# TsinghuaDoor_bottom.net
KiCad netlist of a schematic drawn in Altium Designer
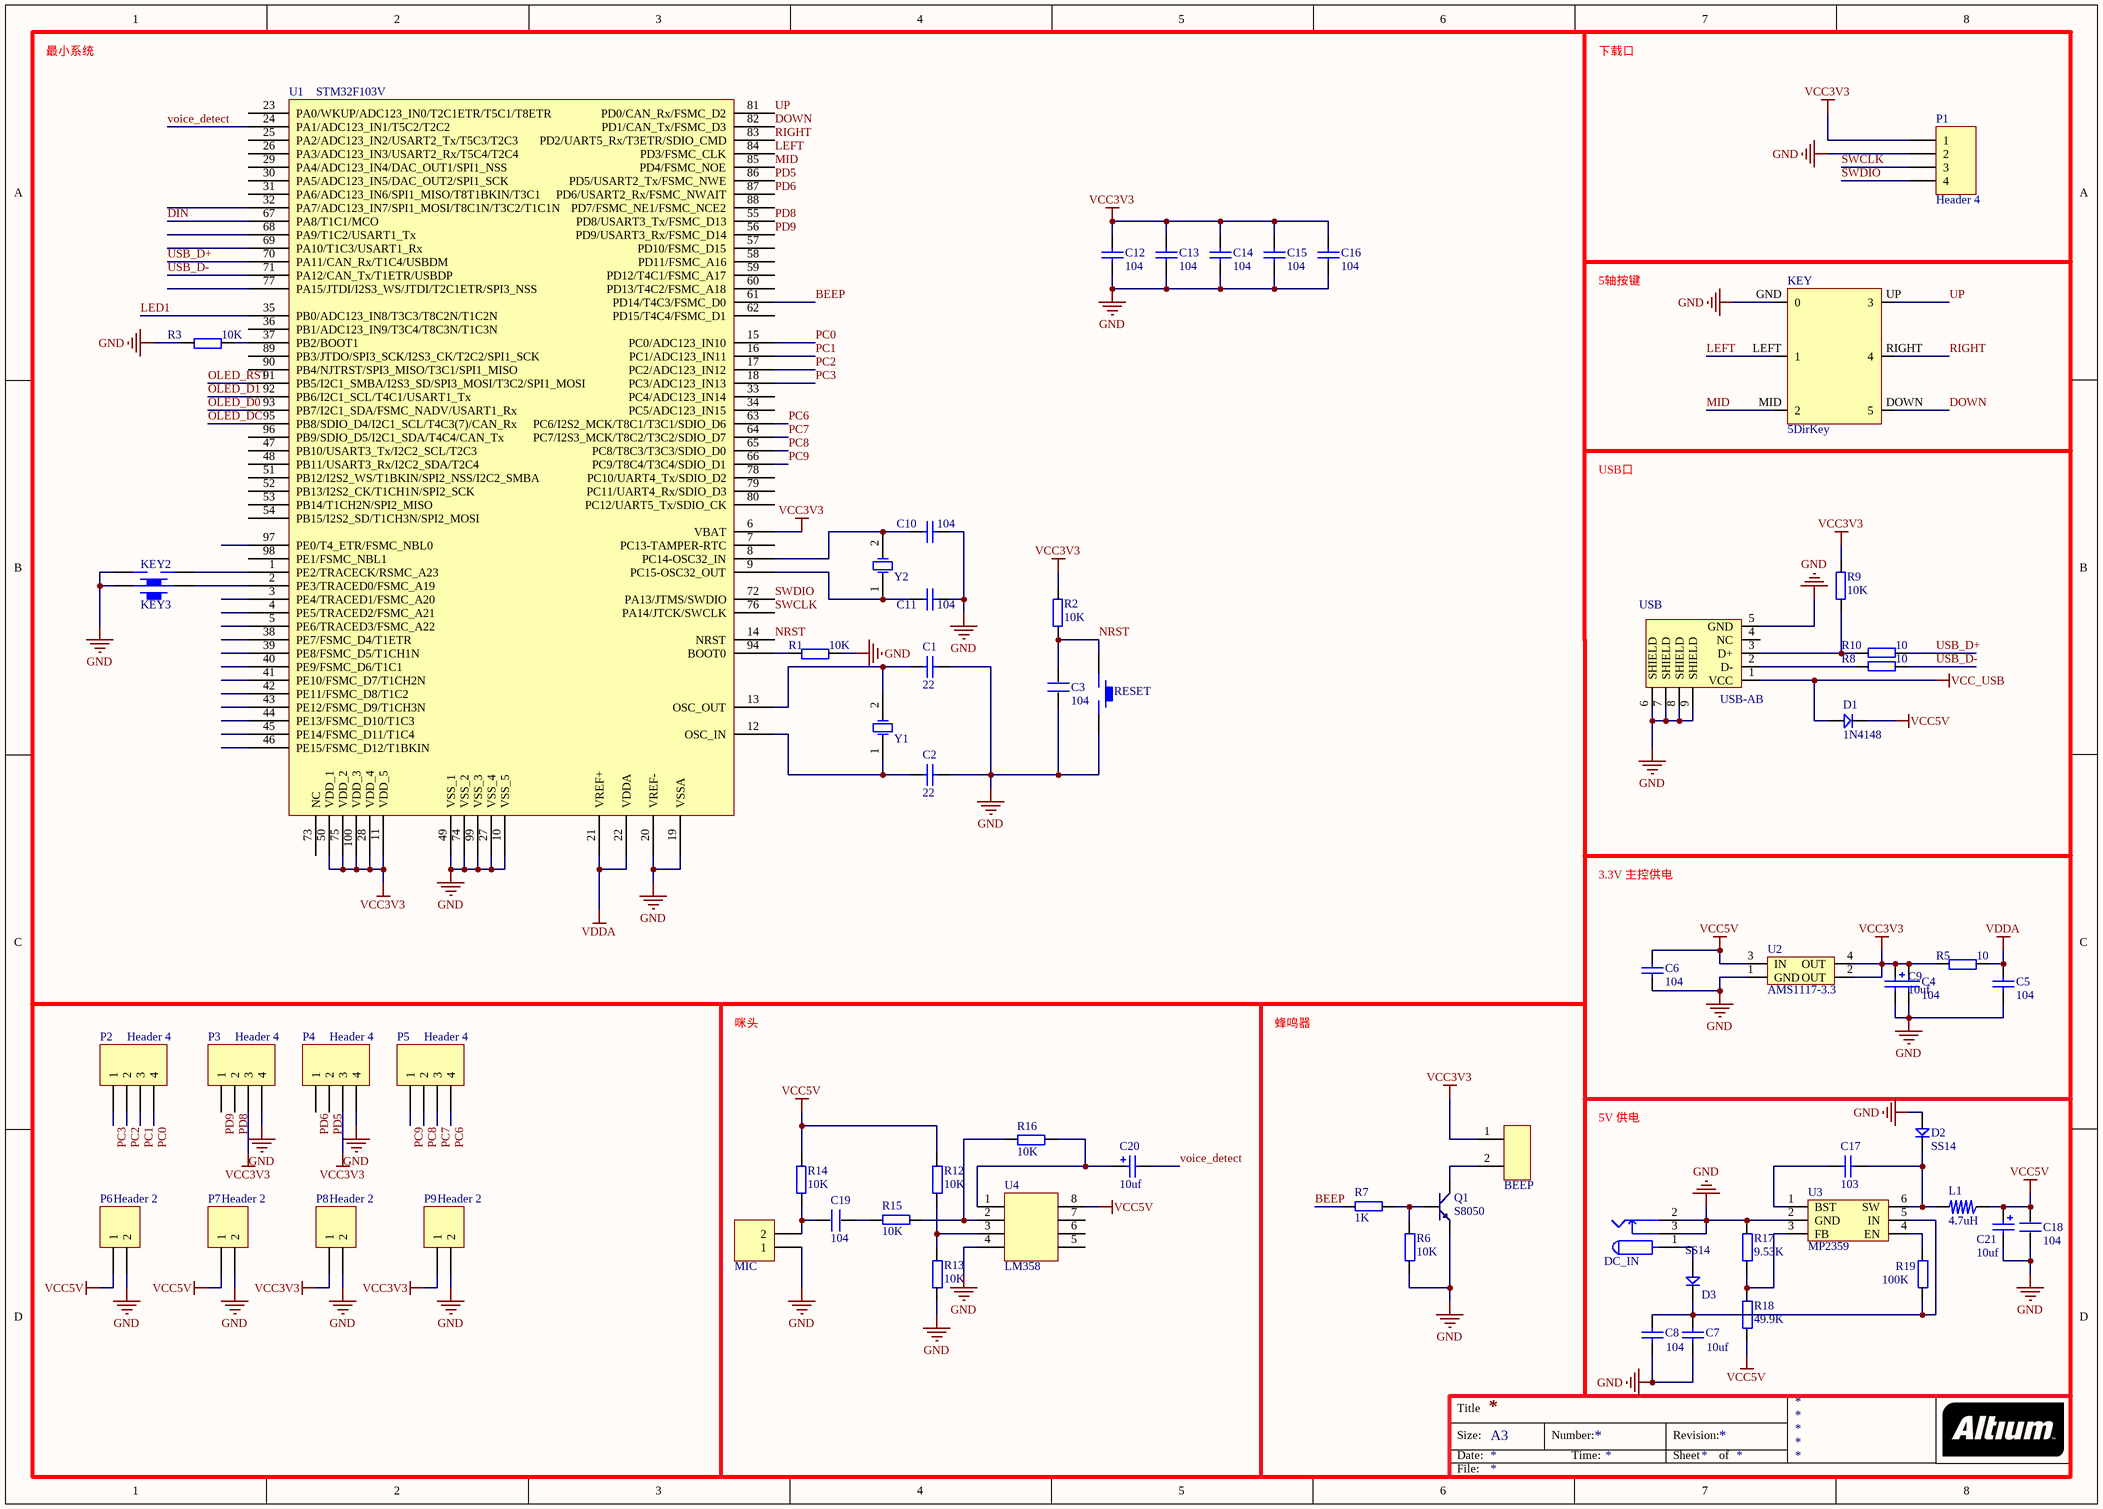
[diagram p0: TsinghuaDoor_bottom.SchDoc]

(export (version "E")
  (design (tool "Eeschema 10.0.6"))
  (components
    (comp (ref "BEEP") (value "蜂鸣器") (footprint "蜂鸣器-7.6mm") (libsource (lib "常用元件集成库") (part "蜂鸣器")))
    (comp (ref "C1")
      (value "22")
      (footprint "cap_0603 - duplicate")
      (description "Capacitor")
      (fields (field (name "Comment") "Cap") (field (name "PUBLISHER") "Altium Limited"))
      (libsource (lib "常用元件集成库") (part "Cap"))
    )
    (comp (ref "C2")
      (value "22")
      (footprint "cap_0603 - duplicate")
      (description "Capacitor")
      (fields (field (name "Comment") "Cap") (field (name "PUBLISHER") "Altium Limited"))
      (libsource (lib "常用元件集成库") (part "Cap"))
    )
    (comp (ref "C3") (value "104") (footprint "0603P") (libsource (lib "阿波罗STM32F4&F7底板封装库") (part "C")))
    (comp (ref "C4")
      (value "104")
      (footprint "cap_0603 - duplicate")
      (description "Capacitor")
      (fields (field (name "Comment") "Cap") (field (name "PUBLISHER") "Altium Limited"))
      (libsource (lib "常用元件集成库") (part "Cap"))
    )
    (comp (ref "C5")
      (value "104")
      (footprint "cap_0603 - duplicate")
      (description "Capacitor")
      (fields (field (name "Comment") "Cap") (field (name "PUBLISHER") "Altium Limited"))
      (libsource (lib "常用元件集成库") (part "Cap"))
    )
    (comp (ref "C6")
      (value "104")
      (footprint "cap_0603 - duplicate")
      (description "Capacitor")
      (fields (field (name "Comment") "Cap") (field (name "PUBLISHER") "Altium Limited"))
      (libsource (lib "常用元件集成库") (part "Cap"))
    )
    (comp (ref "C7")
      (value "10uf")
      (footprint "电容-0805")
      (description "Capacitor")
      (fields (field (name "Comment") "Cap") (field (name "PUBLISHER") "Altium Limited"))
      (libsource (lib "常用元件集成库") (part "Cap"))
    )
    (comp (ref "C8")
      (value "104")
      (footprint "电容-0805")
      (description "Capacitor")
      (fields (field (name "Comment") "Cap") (field (name "PUBLISHER") "Altium Limited"))
      (libsource (lib "常用元件集成库") (part "Cap"))
    )
    (comp (ref "C9")
      (value "10uf")
      (footprint "电容-6032")
      (description "Polarized Capacitor (Radial)")
      (fields (field (name "Comment") "Cap Pol") (field (name "PUBLISHER") "Altium Limited"))
      (libsource (lib "常用元件集成库") (part "Cap Pol"))
    )
    (comp (ref "C10")
      (value "104")
      (footprint "cap_0603 - duplicate")
      (description "Capacitor")
      (fields (field (name "Comment") "Cap") (field (name "PUBLISHER") "Altium Limited"))
      (libsource (lib "常用元件集成库") (part "Cap"))
    )
    (comp (ref "C11")
      (value "104")
      (footprint "cap_0603 - duplicate")
      (description "Capacitor")
      (fields (field (name "Comment") "Cap") (field (name "PUBLISHER") "Altium Limited"))
      (libsource (lib "常用元件集成库") (part "Cap"))
    )
    (comp (ref "C12")
      (value "104")
      (footprint "cap_0603 - duplicate")
      (description "Capacitor")
      (fields (field (name "Comment") "Cap") (field (name "PUBLISHER") "Altium Limited"))
      (libsource (lib "常用元件集成库") (part "Cap"))
    )
    (comp (ref "C13")
      (value "104")
      (footprint "cap_0603 - duplicate")
      (description "Capacitor")
      (fields (field (name "Comment") "Cap") (field (name "PUBLISHER") "Altium Limited"))
      (libsource (lib "常用元件集成库") (part "Cap"))
    )
    (comp (ref "C14")
      (value "104")
      (footprint "cap_0603 - duplicate")
      (description "Capacitor")
      (fields (field (name "Comment") "Cap") (field (name "PUBLISHER") "Altium Limited"))
      (libsource (lib "常用元件集成库") (part "Cap"))
    )
    (comp (ref "C15")
      (value "104")
      (footprint "cap_0603 - duplicate")
      (description "Capacitor")
      (fields (field (name "Comment") "Cap") (field (name "PUBLISHER") "Altium Limited"))
      (libsource (lib "常用元件集成库") (part "Cap"))
    )
    (comp (ref "C16")
      (value "104")
      (footprint "cap_0603 - duplicate")
      (description "Capacitor")
      (fields (field (name "Comment") "Cap") (field (name "PUBLISHER") "Altium Limited"))
      (libsource (lib "常用元件集成库") (part "Cap"))
    )
    (comp (ref "C17")
      (value "103")
      (footprint "电容-0805")
      (description "Capacitor")
      (fields (field (name "Comment") "Cap") (field (name "PUBLISHER") "Altium Limited"))
      (libsource (lib "常用元件集成库") (part "Cap"))
    )
    (comp (ref "C18") (value "104") (footprint "0603P") (libsource (lib "阿波罗STM32F4&F7底板封装库") (part "C")))
    (comp (ref "C19") (value "104") (footprint "1206") (libsource (lib "阿波罗STM32F4&F7底板封装库") (part "C")))
    (comp (ref "C20")
      (value "10uf")
      (footprint "电容-3528")
      (description "Polarized Capacitor (Radial)")
      (fields (field (name "Comment") "Cap Pol") (field (name "PUBLISHER") "Altium Limited"))
      (libsource (lib "常用元件集成库") (part "Cap Pol"))
    )
    (comp (ref "C21")
      (value "10uf")
      (footprint "电容-6032")
      (description "Polarized Capacitor (Radial)")
      (fields (field (name "Comment") "Cap Pol") (field (name "PUBLISHER") "Altium Limited"))
      (libsource (lib "常用元件集成库") (part "Cap Pol"))
    )
    (comp (ref "D1")
      (value "1N4148")
      (footprint "DIODE_3*5.3")
      (libsource (lib "阿波罗STM32F4&F7底板封装库") (part "D"))
    )
    (comp (ref "D2")
      (value "SS14")
      (footprint "DIODE_3*5.3")
      (libsource (lib "阿波罗STM32F4&F7底板封装库") (part "D"))
    )
    (comp (ref "D3")
      (value "SS14")
      (footprint "DIODE_3*5.3")
      (libsource (lib "阿波罗STM32F4&F7底板封装库") (part "D"))
    )
    (comp (ref "DC_IN")
      (value "POWER")
      (footprint "DC10B")
      (libsource (lib "阿波罗STM32F4&F7底板封装库") (part "POW"))
    )
    (comp (ref "KEY") (value "5DirKey") (footprint "5DirKey") (libsource (lib "常用元件集成库") (part "5DirKey")))
    (comp (ref "KEY2")
      (value "KEY_M")
      (footprint "KEY_M")
      (libsource (lib "阿波罗STM32F4&F7底板封装库") (part "KEY_M"))
    )
    (comp (ref "KEY3")
      (value "KEY_M")
      (footprint "KEY_M")
      (libsource (lib "阿波罗STM32F4&F7底板封装库") (part "KEY_M"))
    )
    (comp (ref "L1")
      (value "4.7uH")
      (footprint "L_SOP74")
      (libsource (lib "阿波罗STM32F4&F7底板封装库") (part "L_SOP"))
    )
    (comp (ref "MIC")
      (value "VREF_SEL")
      (footprint "HDR1X2")
      (description "Header, 2-Pin")
      (fields (field (name "PUBLISHER") "Altium Limited"))
      (libsource (lib "阿波罗STM32F4&F7底板封装库") (part "Header 2"))
    )
    (comp (ref "P1")
      (value "Header 4")
      (footprint "HDR1X4")
      (description "Header, 4-Pin")
      (fields (field (name "PUBLISHER") "Altium Limited"))
      (libsource (lib "阿波罗STM32F4&F7底板封装库") (part "Header 4"))
    )
    (comp (ref "P2")
      (value "Header 4")
      (footprint "Header-1*4-2.54mm")
      (description "Header, 4-Pin")
      (fields (field (name "PUBLISHER") "Altium Limited"))
      (libsource (lib "接插件集成库") (part "Header 4"))
    )
    (comp (ref "P3")
      (value "Header 4")
      (footprint "Header-1*4-2.54mm")
      (description "Header, 4-Pin")
      (fields (field (name "PUBLISHER") "Altium Limited"))
      (libsource (lib "接插件集成库") (part "Header 4"))
    )
    (comp (ref "P4")
      (value "Header 4")
      (footprint "Header-1*4-2.54mm")
      (description "Header, 4-Pin")
      (fields (field (name "PUBLISHER") "Altium Limited"))
      (libsource (lib "接插件集成库") (part "Header 4"))
    )
    (comp (ref "P5")
      (value "Header 4")
      (footprint "Header-1*4-2.54mm")
      (description "Header, 4-Pin")
      (fields (field (name "PUBLISHER") "Altium Limited"))
      (libsource (lib "接插件集成库") (part "Header 4"))
    )
    (comp (ref "P6")
      (value "Header 2")
      (footprint "Header-1*2-2.54mm")
      (description "Header, 2-Pin")
      (fields (field (name "PUBLISHER") "Altium Limited"))
      (libsource (lib "接插件集成库") (part "Header 2"))
    )
    (comp (ref "P7")
      (value "Header 2")
      (footprint "Header-1*2-2.54mm")
      (description "Header, 2-Pin")
      (fields (field (name "PUBLISHER") "Altium Limited"))
      (libsource (lib "接插件集成库") (part "Header 2"))
    )
    (comp (ref "P8")
      (value "Header 2")
      (footprint "Header-1*2-2.54mm")
      (description "Header, 2-Pin")
      (fields (field (name "PUBLISHER") "Altium Limited"))
      (libsource (lib "接插件集成库") (part "Header 2"))
    )
    (comp (ref "P9")
      (value "Header 2")
      (footprint "Header-1*2-2.54mm")
      (description "Header, 2-Pin")
      (fields (field (name "PUBLISHER") "Altium Limited"))
      (libsource (lib "接插件集成库") (part "Header 2"))
    )
    (comp (ref "Q1")
      (value "S8050")
      (footprint "SOT-23R")
      (description "8050/BCW846/BCW847")
      (libsource (lib "阿波罗STM32F4&F7底板封装库") (part "NPN"))
    )
    (comp (ref "R1") (value "10K") (footprint "0603P") (libsource (lib "阿波罗STM32F4&F7底板封装库") (part "R")))
    (comp (ref "R2") (value "10K") (footprint "0603P") (libsource (lib "阿波罗STM32F4&F7底板封装库") (part "R")))
    (comp (ref "R3") (value "10K") (footprint "0603P") (libsource (lib "阿波罗STM32F4&F7底板封装库") (part "R")))
    (comp (ref "R5") (value "10") (footprint "0603P") (libsource (lib "阿波罗STM32F4&F7底板封装库") (part "R")))
    (comp (ref "R6") (value "10K") (footprint "0603P") (libsource (lib "阿波罗STM32F4&F7底板封装库") (part "R")))
    (comp (ref "R7") (value "1K") (footprint "0603P") (libsource (lib "阿波罗STM32F4&F7底板封装库") (part "R")))
    (comp (ref "R8") (value "10") (footprint "0603P") (libsource (lib "阿波罗STM32F4&F7底板封装库") (part "R")))
    (comp (ref "R9") (value "10K") (footprint "0603P") (libsource (lib "阿波罗STM32F4&F7底板封装库") (part "R")))
    (comp (ref "R10") (value "10") (footprint "0603P") (libsource (lib "阿波罗STM32F4&F7底板封装库") (part "R")))
    (comp (ref "R12") (value "10K") (footprint "0603P") (libsource (lib "阿波罗STM32F4&F7底板封装库") (part "R")))
    (comp (ref "R13") (value "10K") (footprint "0603P") (libsource (lib "阿波罗STM32F4&F7底板封装库") (part "R")))
    (comp (ref "R14") (value "10K") (footprint "0603P") (libsource (lib "阿波罗STM32F4&F7底板封装库") (part "R")))
    (comp (ref "R15") (value "10K") (footprint "0603P") (libsource (lib "阿波罗STM32F4&F7底板封装库") (part "R")))
    (comp (ref "R16") (value "10K") (footprint "0603P") (libsource (lib "阿波罗STM32F4&F7底板封装库") (part "R")))
    (comp (ref "R17") (value "9.53K") (footprint "0603P") (libsource (lib "阿波罗STM32F4&F7底板封装库") (part "R")))
    (comp (ref "R18") (value "49.9K") (footprint "0603P") (libsource (lib "阿波罗STM32F4&F7底板封装库") (part "R")))
    (comp (ref "R19") (value "100K") (footprint "0603P") (libsource (lib "阿波罗STM32F4&F7底板封装库") (part "R")))
    (comp (ref "RESET") (value "KEY_M") (footprint "KEY_M") (libsource (lib "") (part "KEY_M_1")))
    (comp (ref "U1")
      (value "STM32F103V")
      (footprint "LQFP-100_M")
      (description "STM32单片机100引脚")
      (libsource (lib "主控芯片集成库") (part "STM32F103V"))
    )
    (comp (ref "U2")
      (value "AMS1117-3.3")
      (footprint "AMS1117")
      (libsource (lib "阿波罗STM32F4&F7底板封装库") (part "AMS1117"))
    )
    (comp (ref "U3")
      (value "MP2359")
      (footprint "SOT-23-6")
      (description "DC DC Step Down IC")
      (libsource (lib "阿波罗STM32F4&F7底板封装库") (part "MP2359"))
    )
    (comp (ref "U4") (value "LM358") (footprint "SOP-8-4mm") (libsource (lib "IC集成库") (part "IC-8")))
    (comp (ref "USB")
      (value "USB-AB")
      (footprint "USB_AB - 5S - B")
      (description "MicroUSB")
      (libsource (lib "UWB") (part "USB-AB"))
    )
    (comp (ref "Y1")
      (value "晶振")
      (footprint "晶振-DIP2-5.08")
      (description "Crystal Oscillator")
      (fields (field (name "PUBLISHER") "Altium Limited"))
      (libsource (lib "常用元件集成库") (part "晶振"))
    )
    (comp (ref "Y2")
      (value "晶振")
      (footprint "圆柱晶振")
      (description "Crystal Oscillator")
      (fields (field (name "PUBLISHER") "Altium Limited"))
      (libsource (lib "常用元件集成库") (part "晶振"))
    )
  )
  (nets
    (net (code "1") (name "/BEEP") (class "Default")
      (node (ref "R7") (pin "2") (pintype "passive"))
      (node (ref "U1") (pin "61") (pinfunction "PD14/T4C3/FSMC_D0_61") (pintype "passive"))
    )
    (net (code "2") (name "/DIN") (class "Default")
      (node (ref "U1") (pin "67") (pinfunction "PA8/T1C1/MCO_67") (pintype "passive"))
    )
    (net (code "3") (name "/DOWN") (class "Default")
      (node (ref "KEY") (pin "DOWN") (pinfunction "5_DOWN") (pintype "passive"))
      (node (ref "U1") (pin "82") (pinfunction "PD1/CAN_Tx/FSMC_D3_82") (pintype "passive"))
    )
    (net (code "4") (name "/LED1") (class "Default")
      (node (ref "U1") (pin "35") (pinfunction "PB0/ADC123_IN8/T3C3/T8C2N/T1C2N_35") (pintype "passive"))
    )
    (net (code "5") (name "/LEFT") (class "Default")
      (node (ref "KEY") (pin "LEFT") (pinfunction "1_LEFT") (pintype "passive"))
      (node (ref "U1") (pin "84") (pinfunction "PD3/FSMC_CLK_84") (pintype "passive"))
    )
    (net (code "6") (name "/MID") (class "Default")
      (node (ref "KEY") (pin "MID") (pinfunction "2_MID") (pintype "passive"))
      (node (ref "U1") (pin "85") (pinfunction "PD4/FSMC_NOE_85") (pintype "passive"))
    )
    (net (code "7") (name "/NRST") (class "Default")
      (node (ref "C3") (pin "2") (pintype "passive"))
      (node (ref "R2") (pin "2") (pintype "passive"))
      (node (ref "RESET") (pin "1") (pinfunction "1_1") (pintype "passive"))
      (node (ref "U1") (pin "14") (pinfunction "NRST_14") (pintype "passive"))
    )
    (net (code "8") (name "/OLED_D0") (class "Default")
      (node (ref "U1") (pin "93") (pinfunction "PB7/I2C1_SDA/FSMC_NADV/USART1_Rx_93") (pintype "passive"))
    )
    (net (code "9") (name "/OLED_D1") (class "Default")
      (node (ref "U1") (pin "92") (pinfunction "PB6/I2C1_SCL/T4C1/USART1_Tx_92") (pintype "passive"))
    )
    (net (code "10") (name "/OLED_DC") (class "Default")
      (node (ref "U1") (pin "95") (pinfunction "PB8/SDIO_D4/I2C1_SCL/T4C3(7)/CAN_Rx_95") (pintype "passive"))
    )
    (net (code "11") (name "/OLED_RST") (class "Default")
      (node (ref "U1") (pin "91") (pinfunction "PB5/I2C1_SMBA/I2S3_SD/SPI3_MOSI/T3C2/SPI1_MOSI_91") (pintype "passive"))
    )
    (net (code "12") (name "/PC0") (class "Default")
      (node (ref "P2") (pin "4") (pinfunction "4_4") (pintype "passive"))
      (node (ref "U1") (pin "15") (pinfunction "PC0/ADC123_IN10_15") (pintype "passive"))
    )
    (net (code "13") (name "/PC1") (class "Default")
      (node (ref "P2") (pin "3") (pinfunction "3_3") (pintype "passive"))
      (node (ref "U1") (pin "16") (pinfunction "PC1/ADC123_IN11_16") (pintype "passive"))
    )
    (net (code "14") (name "/PC2") (class "Default")
      (node (ref "P2") (pin "2") (pinfunction "2_2") (pintype "passive"))
      (node (ref "U1") (pin "17") (pinfunction "PC2/ADC123_IN12_17") (pintype "passive"))
    )
    (net (code "15") (name "/PC3") (class "Default")
      (node (ref "P2") (pin "1") (pinfunction "1_1") (pintype "passive"))
      (node (ref "U1") (pin "18") (pinfunction "PC3/ADC123_IN13_18") (pintype "passive"))
    )
    (net (code "16") (name "/PC6") (class "Default")
      (node (ref "P5") (pin "4") (pinfunction "4_4") (pintype "passive"))
      (node (ref "U1") (pin "63") (pinfunction "PC6/I2S2_MCK/T8C1/T3C1/SDIO_D6_63") (pintype "passive"))
    )
    (net (code "17") (name "/PC7") (class "Default")
      (node (ref "P5") (pin "3") (pinfunction "3_3") (pintype "passive"))
      (node (ref "U1") (pin "64") (pinfunction "PC7/I2S3_MCK/T8C2/T3C2/SDIO_D7_64") (pintype "passive"))
    )
    (net (code "18") (name "/PC8") (class "Default")
      (node (ref "P5") (pin "2") (pinfunction "2_2") (pintype "passive"))
      (node (ref "U1") (pin "65") (pinfunction "PC8/T8C3/T3C3/SDIO_D0_65") (pintype "passive"))
    )
    (net (code "19") (name "/PC9") (class "Default")
      (node (ref "P5") (pin "1") (pinfunction "1_1") (pintype "passive"))
      (node (ref "U1") (pin "66") (pinfunction "PC9/T8C4/T3C4/SDIO_D1_66") (pintype "passive"))
    )
    (net (code "20") (name "/PD5") (class "Default")
      (node (ref "P4") (pin "2") (pinfunction "2_2") (pintype "passive"))
      (node (ref "U1") (pin "86") (pinfunction "PD5/USART2_Tx/FSMC_NWE_86") (pintype "passive"))
    )
    (net (code "21") (name "/PD6") (class "Default")
      (node (ref "P4") (pin "1") (pinfunction "1_1") (pintype "passive"))
      (node (ref "U1") (pin "87") (pinfunction "PD6/USART2_Rx/FSMC_NWAIT_87") (pintype "passive"))
    )
    (net (code "22") (name "/PD8") (class "Default")
      (node (ref "P3") (pin "2") (pinfunction "2_2") (pintype "passive"))
      (node (ref "U1") (pin "55") (pinfunction "PD8/USART3_Tx/FSMC_D13_55") (pintype "passive"))
    )
    (net (code "23") (name "/PD9") (class "Default")
      (node (ref "P3") (pin "1") (pinfunction "1_1") (pintype "passive"))
      (node (ref "U1") (pin "56") (pinfunction "PD9/USART3_Rx/FSMC_D14_56") (pintype "passive"))
    )
    (net (code "24") (name "/RIGHT") (class "Default")
      (node (ref "KEY") (pin "RIGHT") (pinfunction "4_RIGHT") (pintype "passive"))
      (node (ref "U1") (pin "83") (pinfunction "PD2/UART5_Rx/T3ETR/SDIO_CMD_83") (pintype "passive"))
    )
    (net (code "25") (name "/SWCLK") (class "Default")
      (node (ref "P1") (pin "3") (pinfunction "3_3") (pintype "passive"))
      (node (ref "U1") (pin "76") (pinfunction "PA14/JTCK/SWCLK_76") (pintype "passive"))
    )
    (net (code "26") (name "/SWDIO") (class "Default")
      (node (ref "P1") (pin "4") (pinfunction "4_4") (pintype "passive"))
      (node (ref "U1") (pin "72") (pinfunction "PA13/JTMS/SWDIO_72") (pintype "passive"))
    )
    (net (code "27") (name "/UP") (class "Default")
      (node (ref "KEY") (pin "UP") (pinfunction "3_UP") (pintype "passive"))
      (node (ref "U1") (pin "81") (pinfunction "PD0/CAN_Rx/FSMC_D2_81") (pintype "passive"))
    )
    (net (code "28") (name "/USB_D+") (class "Default")
      (node (ref "R10") (pin "1") (pintype "passive"))
      (node (ref "U1") (pin "70") (pinfunction "PA11/CAN_Rx/T1C4/USBDM_70") (pintype "passive"))
    )
    (net (code "29") (name "/USB_D-") (class "Default")
      (node (ref "R8") (pin "1") (pintype "passive"))
      (node (ref "U1") (pin "71") (pinfunction "PA12/CAN_Tx/T1ETR/USBDP_71") (pintype "passive"))
    )
    (net (code "30") (name "/voice_detect") (class "Default")
      (node (ref "C20") (pin "2") (pinfunction "2_2") (pintype "passive"))
      (node (ref "U1") (pin "24") (pinfunction "PA1/ADC123_IN1/T5C2/T2C2_24") (pintype "passive"))
    )
    (net (code "31") (name "GND") (class "Default")
      (node (ref "C1") (pin "1") (pinfunction "1_1") (pintype "passive"))
      (node (ref "C10") (pin "2") (pinfunction "2_2") (pintype "passive"))
      (node (ref "C11") (pin "2") (pinfunction "2_2") (pintype "passive"))
      (node (ref "C12") (pin "1") (pinfunction "1_1") (pintype "passive"))
      (node (ref "C13") (pin "1") (pinfunction "1_1") (pintype "passive"))
      (node (ref "C14") (pin "1") (pinfunction "1_1") (pintype "passive"))
      (node (ref "C15") (pin "1") (pinfunction "1_1") (pintype "passive"))
      (node (ref "C16") (pin "1") (pinfunction "1_1") (pintype "passive"))
      (node (ref "C18") (pin "1") (pintype "passive"))
      (node (ref "C2") (pin "1") (pinfunction "1_1") (pintype "passive"))
      (node (ref "C21") (pin "2") (pinfunction "2_2") (pintype "passive"))
      (node (ref "C3") (pin "1") (pintype "passive"))
      (node (ref "C4") (pin "1") (pinfunction "1_1") (pintype "passive"))
      (node (ref "C5") (pin "1") (pinfunction "1_1") (pintype "passive"))
      (node (ref "C6") (pin "1") (pinfunction "1_1") (pintype "passive"))
      (node (ref "C7") (pin "1") (pinfunction "1_1") (pintype "passive"))
      (node (ref "C8") (pin "1") (pinfunction "1_1") (pintype "passive"))
      (node (ref "C9") (pin "2") (pinfunction "2_2") (pintype "passive"))
      (node (ref "D2") (pin "1") (pintype "passive"))
      (node (ref "DC_IN") (pin "2") (pintype "passive"))
      (node (ref "DC_IN") (pin "3") (pintype "passive"))
      (node (ref "KEY") (pin "GND") (pinfunction "0_GND") (pintype "passive"))
      (node (ref "KEY2") (pin "2") (pinfunction "2_2") (pintype "passive"))
      (node (ref "KEY3") (pin "2") (pinfunction "2_2") (pintype "passive"))
      (node (ref "MIC") (pin "1") (pinfunction "1_1") (pintype "passive"))
      (node (ref "P1") (pin "2") (pinfunction "2_2") (pintype "passive"))
      (node (ref "P3") (pin "4") (pinfunction "4_4") (pintype "passive"))
      (node (ref "P4") (pin "4") (pinfunction "4_4") (pintype "passive"))
      (node (ref "P6") (pin "2") (pinfunction "2_2") (pintype "passive"))
      (node (ref "P7") (pin "2") (pinfunction "2_2") (pintype "passive"))
      (node (ref "P8") (pin "2") (pinfunction "2_2") (pintype "passive"))
      (node (ref "P9") (pin "2") (pinfunction "2_2") (pintype "passive"))
      (node (ref "Q1") (pin "1") (pinfunction "E_1") (pintype "passive"))
      (node (ref "R1") (pin "2") (pintype "passive"))
      (node (ref "R13") (pin "1") (pintype "passive"))
      (node (ref "R17") (pin "2") (pintype "passive"))
      (node (ref "R3") (pin "1") (pintype "passive"))
      (node (ref "R6") (pin "1") (pintype "passive"))
      (node (ref "RESET") (pin "2") (pinfunction "2_2") (pintype "passive"))
      (node (ref "U1") (pin "10") (pinfunction "VSS_5_10") (pintype "passive"))
      (node (ref "U1") (pin "19") (pinfunction "VSSA_19") (pintype "passive"))
      (node (ref "U1") (pin "20") (pinfunction "VREF-_20") (pintype "passive"))
      (node (ref "U1") (pin "27") (pinfunction "VSS_4_27") (pintype "passive"))
      (node (ref "U1") (pin "49") (pinfunction "VSS_1_49") (pintype "passive"))
      (node (ref "U1") (pin "74") (pinfunction "VSS_2_74") (pintype "passive"))
      (node (ref "U1") (pin "99") (pinfunction "VSS_3_99") (pintype "passive"))
      (node (ref "U2") (pin "1") (pinfunction "GND_1") (pintype "passive"))
      (node (ref "U3") (pin "2") (pinfunction "GND_2") (pintype "passive"))
      (node (ref "U4") (pin "4") (pintype "passive"))
      (node (ref "USB") (pin "5") (pinfunction "GND_5") (pintype "passive"))
      (node (ref "USB") (pin "6") (pinfunction "SHIELD_6") (pintype "passive"))
      (node (ref "USB") (pin "7") (pinfunction "SHIELD_7") (pintype "passive"))
      (node (ref "USB") (pin "8") (pinfunction "SHIELD_8") (pintype "passive"))
      (node (ref "USB") (pin "9") (pinfunction "SHIELD_9") (pintype "passive"))
    )
    (net (code "32") (name "Net-(BEEP-20)") (class "Default")
      (node (ref "BEEP") (pin "2") (pinfunction "20_2") (pintype "passive"))
      (node (ref "Q1") (pin "3") (pinfunction "C_3") (pintype "passive"))
    )
    (net (code "33") (name "Net-(C19-Pad1)") (class "Default")
      (node (ref "C19") (pin "1") (pintype "passive"))
      (node (ref "MIC") (pin "2") (pinfunction "2_2") (pintype "passive"))
      (node (ref "R14") (pin "2") (pintype "passive"))
    )
    (net (code "34") (name "Net-(C19-Pad2)") (class "Default")
      (node (ref "C19") (pin "2") (pintype "passive"))
      (node (ref "R15") (pin "2") (pintype "passive"))
    )
    (net (code "35") (name "Net-(C20-Pad1)") (class "Default")
      (node (ref "C20") (pin "1") (pinfunction "1_1") (pintype "passive"))
      (node (ref "R16") (pin "2") (pintype "passive"))
      (node (ref "U4") (pin "1") (pintype "passive"))
    )
    (net (code "36") (name "Net-(D3-Pad1)") (class "Default")
      (node (ref "D3") (pin "1") (pintype "passive"))
      (node (ref "DC_IN") (pin "1") (pintype "passive"))
    )
    (net (code "37") (name "Net-(Q1-B)") (class "Default")
      (node (ref "Q1") (pin "2") (pinfunction "B_2") (pintype "passive"))
      (node (ref "R6") (pin "2") (pintype "passive"))
      (node (ref "R7") (pin "1") (pintype "passive"))
    )
    (net (code "38") (name "Net-(R12-Pad1)") (class "Default")
      (node (ref "R12") (pin "1") (pintype "passive"))
      (node (ref "R13") (pin "2") (pintype "passive"))
      (node (ref "U4") (pin "3") (pintype "passive"))
    )
    (net (code "39") (name "Net-(R15-Pad1)") (class "Default")
      (node (ref "R15") (pin "1") (pintype "passive"))
      (node (ref "R16") (pin "1") (pintype "passive"))
      (node (ref "U4") (pin "2") (pintype "passive"))
    )
    (net (code "40") (name "Net-(U1-BOOT0)") (class "Default")
      (node (ref "R1") (pin "1") (pintype "passive"))
      (node (ref "U1") (pin "94") (pinfunction "BOOT0_94") (pintype "passive"))
    )
    (net (code "41") (name "Net-(U1-OSC_IN)") (class "Default")
      (node (ref "C2") (pin "2") (pinfunction "2_2") (pintype "passive"))
      (node (ref "U1") (pin "12") (pinfunction "OSC_IN_12") (pintype "passive"))
      (node (ref "Y1") (pin "1") (pinfunction "OSC1_1") (pintype "passive"))
    )
    (net (code "42") (name "Net-(U1-OSC_OUT)") (class "Default")
      (node (ref "C1") (pin "2") (pinfunction "2_2") (pintype "passive"))
      (node (ref "U1") (pin "13") (pinfunction "OSC_OUT_13") (pintype "passive"))
      (node (ref "Y1") (pin "2") (pinfunction "OSC2_2") (pintype "passive"))
    )
    (net (code "43") (name "Net-(U1-PB2{slash}BOOT1)") (class "Default")
      (node (ref "R3") (pin "2") (pintype "passive"))
      (node (ref "U1") (pin "37") (pinfunction "PB2/BOOT1_37") (pintype "passive"))
    )
    (net (code "44") (name "Net-(U1-PC14-OSC32_IN)") (class "Default")
      (node (ref "C10") (pin "1") (pinfunction "1_1") (pintype "passive"))
      (node (ref "U1") (pin "8") (pinfunction "PC14-OSC32_IN_8") (pintype "passive"))
      (node (ref "Y2") (pin "2") (pinfunction "OSC2_2") (pintype "passive"))
    )
    (net (code "45") (name "Net-(U1-PC15-OSC32_OUT)") (class "Default")
      (node (ref "C11") (pin "1") (pinfunction "1_1") (pintype "passive"))
      (node (ref "U1") (pin "9") (pinfunction "PC15-OSC32_OUT_9") (pintype "passive"))
      (node (ref "Y2") (pin "1") (pinfunction "OSC1_1") (pintype "passive"))
    )
    (net (code "46") (name "Net-(U1-PE2{slash}TRACECK{slash}RSMC_A23)") (class "Default")
      (node (ref "KEY2") (pin "1") (pinfunction "1_1") (pintype "passive"))
      (node (ref "U1") (pin "1") (pinfunction "PE2/TRACECK/RSMC_A23_1") (pintype "passive"))
    )
    (net (code "47") (name "Net-(U1-PE3{slash}TRACED0{slash}FSMC_A19)") (class "Default")
      (node (ref "KEY3") (pin "1") (pinfunction "1_1") (pintype "passive"))
      (node (ref "U1") (pin "2") (pinfunction "PE3/TRACED0/FSMC_A19_2") (pintype "passive"))
    )
    (net (code "48") (name "Net-(U3-BST)") (class "Default")
      (node (ref "C17") (pin "1") (pinfunction "1_1") (pintype "passive"))
      (node (ref "U3") (pin "1") (pinfunction "BST_1") (pintype "passive"))
    )
    (net (code "49") (name "Net-(U3-EN)") (class "Default")
      (node (ref "R19") (pin "2") (pintype "passive"))
      (node (ref "U3") (pin "4") (pinfunction "EN_4") (pintype "passive"))
    )
    (net (code "50") (name "Net-(U3-FB)") (class "Default")
      (node (ref "R17") (pin "1") (pintype "passive"))
      (node (ref "R18") (pin "2") (pintype "passive"))
      (node (ref "U3") (pin "3") (pinfunction "FB_3") (pintype "passive"))
    )
    (net (code "51") (name "Net-(U3-IN)") (class "Default")
      (node (ref "C7") (pin "2") (pinfunction "2_2") (pintype "passive"))
      (node (ref "C8") (pin "2") (pinfunction "2_2") (pintype "passive"))
      (node (ref "D3") (pin "2") (pintype "passive"))
      (node (ref "R19") (pin "1") (pintype "passive"))
      (node (ref "U3") (pin "5") (pinfunction "IN_5") (pintype "passive"))
    )
    (net (code "52") (name "Net-(U3-SW)") (class "Default")
      (node (ref "C17") (pin "2") (pinfunction "2_2") (pintype "passive"))
      (node (ref "D2") (pin "2") (pintype "passive"))
      (node (ref "L1") (pin "2") (pinfunction "2_2") (pintype "passive"))
      (node (ref "U3") (pin "6") (pinfunction "SW_6") (pintype "passive"))
    )
    (net (code "53") (name "Net-(USB-D+)") (class "Default")
      (node (ref "R10") (pin "2") (pintype "passive"))
      (node (ref "R9") (pin "2") (pintype "passive"))
      (node (ref "USB") (pin "3") (pinfunction "D+_3") (pintype "passive"))
    )
    (net (code "54") (name "Net-(USB-D-)") (class "Default")
      (node (ref "R8") (pin "2") (pintype "passive"))
      (node (ref "USB") (pin "2") (pinfunction "D-_2") (pintype "passive"))
    )
    (net (code "55") (name "VCC3V3") (class "Default")
      (node (ref "BEEP") (pin "1") (pinfunction "19_1") (pintype "passive"))
      (node (ref "C12") (pin "2") (pinfunction "2_2") (pintype "passive"))
      (node (ref "C13") (pin "2") (pinfunction "2_2") (pintype "passive"))
      (node (ref "C14") (pin "2") (pinfunction "2_2") (pintype "passive"))
      (node (ref "C15") (pin "2") (pinfunction "2_2") (pintype "passive"))
      (node (ref "C16") (pin "2") (pinfunction "2_2") (pintype "passive"))
      (node (ref "C4") (pin "2") (pinfunction "2_2") (pintype "passive"))
      (node (ref "C9") (pin "1") (pinfunction "1_1") (pintype "passive"))
      (node (ref "P1") (pin "1") (pinfunction "1_1") (pintype "passive"))
      (node (ref "P3") (pin "3") (pinfunction "3_3") (pintype "passive"))
      (node (ref "P4") (pin "3") (pinfunction "3_3") (pintype "passive"))
      (node (ref "P8") (pin "1") (pinfunction "1_1") (pintype "passive"))
      (node (ref "P9") (pin "1") (pinfunction "1_1") (pintype "passive"))
      (node (ref "R2") (pin "1") (pintype "passive"))
      (node (ref "R5") (pin "1") (pintype "passive"))
      (node (ref "R9") (pin "1") (pintype "passive"))
      (node (ref "U1") (pin "100") (pinfunction "VDD_3_100") (pintype "passive"))
      (node (ref "U1") (pin "11") (pinfunction "VDD_5_11") (pintype "passive"))
      (node (ref "U1") (pin "28") (pinfunction "VDD_4_28") (pintype "passive"))
      (node (ref "U1") (pin "50") (pinfunction "VDD_1_50") (pintype "passive"))
      (node (ref "U1") (pin "6") (pinfunction "VBAT_6") (pintype "passive"))
      (node (ref "U1") (pin "75") (pinfunction "VDD_2_75") (pintype "passive"))
      (node (ref "U2") (pin "2") (pinfunction "OUT_2") (pintype "passive"))
      (node (ref "U2") (pin "4") (pinfunction "OUT_4") (pintype "passive"))
    )
    (net (code "56") (name "VCC5V") (class "Default")
      (node (ref "C18") (pin "2") (pintype "passive"))
      (node (ref "C21") (pin "1") (pinfunction "1_1") (pintype "passive"))
      (node (ref "C6") (pin "2") (pinfunction "2_2") (pintype "passive"))
      (node (ref "D1") (pin "2") (pintype "passive"))
      (node (ref "L1") (pin "1") (pinfunction "1_1") (pintype "passive"))
      (node (ref "P6") (pin "1") (pinfunction "1_1") (pintype "passive"))
      (node (ref "P7") (pin "1") (pinfunction "1_1") (pintype "passive"))
      (node (ref "R12") (pin "2") (pintype "passive"))
      (node (ref "R14") (pin "1") (pintype "passive"))
      (node (ref "R18") (pin "1") (pintype "passive"))
      (node (ref "U2") (pin "3") (pinfunction "IN_3") (pintype "passive"))
      (node (ref "U4") (pin "8") (pintype "passive"))
    )
    (net (code "57") (name "VCC_USB") (class "Default")
      (node (ref "D1") (pin "1") (pintype "passive"))
      (node (ref "USB") (pin "1") (pinfunction "VCC_1") (pintype "passive"))
    )
    (net (code "58") (name "VDDA") (class "Default")
      (node (ref "C5") (pin "2") (pinfunction "2_2") (pintype "passive"))
      (node (ref "R5") (pin "2") (pintype "passive"))
      (node (ref "U1") (pin "21") (pinfunction "VREF+_21") (pintype "passive"))
      (node (ref "U1") (pin "22") (pinfunction "VDDA_22") (pintype "passive"))
    )
    (net (code "59") (name "unconnected-(U1-NC-Pad73)") (class "Default")
      (node (ref "U1") (pin "73") (pinfunction "NC_73") (pintype "passive"))
    )
    (net (code "60") (name "unconnected-(U1-PA0{slash}WKUP{slash}ADC123_IN0{slash}T2C1ETR{slash}T5C1{slash}T8ETR-Pad23)") (class "Default")
      (node (ref "U1") (pin "23") (pinfunction "PA0/WKUP/ADC123_IN0/T2C1ETR/T5C1/T8ETR_23") (pintype "passive"))
    )
    (net (code "61") (name "unconnected-(U1-PA2{slash}ADC123_IN2{slash}USART2_Tx{slash}T5C3{slash}T2C3-Pad25)") (class "Default")
      (node (ref "U1") (pin "25") (pinfunction "PA2/ADC123_IN2/USART2_Tx/T5C3/T2C3_25") (pintype "passive"))
    )
    (net (code "62") (name "unconnected-(U1-PA3{slash}ADC123_IN3{slash}USART2_Rx{slash}T5C4{slash}T2C4-Pad26)") (class "Default")
      (node (ref "U1") (pin "26") (pinfunction "PA3/ADC123_IN3/USART2_Rx/T5C4/T2C4_26") (pintype "passive"))
    )
    (net (code "63") (name "unconnected-(U1-PA4{slash}ADC123_IN4{slash}DAC_OUT1{slash}SPI1_NSS-Pad29)") (class "Default")
      (node (ref "U1") (pin "29") (pinfunction "PA4/ADC123_IN4/DAC_OUT1/SPI1_NSS_29") (pintype "passive"))
    )
    (net (code "64") (name "unconnected-(U1-PA5{slash}ADC123_IN5{slash}DAC_OUT2{slash}SPI1_SCK-Pad30)") (class "Default")
      (node (ref "U1") (pin "30") (pinfunction "PA5/ADC123_IN5/DAC_OUT2/SPI1_SCK_30") (pintype "passive"))
    )
    (net (code "65") (name "unconnected-(U1-PA6{slash}ADC123_IN6{slash}SPI1_MISO{slash}T8T1BKIN{slash}T3C1-Pad31)") (class "Default")
      (node (ref "U1") (pin "31") (pinfunction "PA6/ADC123_IN6/SPI1_MISO/T8T1BKIN/T3C1_31") (pintype "passive"))
    )
    (net (code "66") (name "unconnected-(U1-PA7{slash}ADC123_IN7{slash}SPI1_MOSI{slash}T8C1N{slash}T3C2{slash}T1C1N-Pad32)") (class "Default")
      (node (ref "U1") (pin "32") (pinfunction "PA7/ADC123_IN7/SPI1_MOSI/T8C1N/T3C2/T1C1N_32") (pintype "passive"))
    )
    (net (code "67") (name "unconnected-(U1-PA9{slash}T1C2{slash}USART1_Tx-Pad68)") (class "Default")
      (node (ref "U1") (pin "68") (pinfunction "PA9/T1C2/USART1_Tx_68") (pintype "passive"))
    )
    (net (code "68") (name "unconnected-(U1-PA10{slash}T1C3{slash}USART1_Rx-Pad69)") (class "Default")
      (node (ref "U1") (pin "69") (pinfunction "PA10/T1C3/USART1_Rx_69") (pintype "passive"))
    )
    (net (code "69") (name "unconnected-(U1-PA15{slash}JTDI{slash}I2S3_WS{slash}JTDI{slash}T2C1ETR{slash}SPI3_NSS-Pad77)") (class "Default")
      (node (ref "U1") (pin "77") (pinfunction "PA15/JTDI/I2S3_WS/JTDI/T2C1ETR/SPI3_NSS_77") (pintype "passive"))
    )
    (net (code "70") (name "unconnected-(U1-PB1{slash}ADC123_IN9{slash}T3C4{slash}T8C3N{slash}T1C3N-Pad36)") (class "Default")
      (node (ref "U1") (pin "36") (pinfunction "PB1/ADC123_IN9/T3C4/T8C3N/T1C3N_36") (pintype "passive"))
    )
    (net (code "71") (name "unconnected-(U1-PB3{slash}JTDO{slash}SPI3_SCK{slash}I2S3_CK{slash}T2C2{slash}SPI1_SCK-Pad89)") (class "Default")
      (node (ref "U1") (pin "89") (pinfunction "PB3/JTDO/SPI3_SCK/I2S3_CK/T2C2/SPI1_SCK_89") (pintype "passive"))
    )
    (net (code "72") (name "unconnected-(U1-PB4{slash}NJTRST{slash}SPI3_MISO{slash}T3C1{slash}SPI1_MISO-Pad90)") (class "Default")
      (node (ref "U1") (pin "90") (pinfunction "PB4/NJTRST/SPI3_MISO/T3C1/SPI1_MISO_90") (pintype "passive"))
    )
    (net (code "73") (name "unconnected-(U1-PB9{slash}SDIO_D5{slash}I2C1_SDA{slash}T4C4{slash}CAN_Tx-Pad96)") (class "Default")
      (node (ref "U1") (pin "96") (pinfunction "PB9/SDIO_D5/I2C1_SDA/T4C4/CAN_Tx_96") (pintype "passive"))
    )
    (net (code "74") (name "unconnected-(U1-PB10{slash}USART3_Tx{slash}I2C2_SCL{slash}T2C3-Pad47)") (class "Default")
      (node (ref "U1") (pin "47") (pinfunction "PB10/USART3_Tx/I2C2_SCL/T2C3_47") (pintype "passive"))
    )
    (net (code "75") (name "unconnected-(U1-PB11{slash}USART3_Rx{slash}I2C2_SDA{slash}T2C4-Pad48)") (class "Default")
      (node (ref "U1") (pin "48") (pinfunction "PB11/USART3_Rx/I2C2_SDA/T2C4_48") (pintype "passive"))
    )
    (net (code "76") (name "unconnected-(U1-PB12{slash}I2S2_WS{slash}T1BKIN{slash}SPI2_NSS{slash}I2C2_SMBA-Pad51)") (class "Default")
      (node (ref "U1") (pin "51") (pinfunction "PB12/I2S2_WS/T1BKIN/SPI2_NSS/I2C2_SMBA_51") (pintype "passive"))
    )
    (net (code "77") (name "unconnected-(U1-PB13{slash}I2S2_CK{slash}T1CH1N{slash}SPI2_SCK-Pad52)") (class "Default")
      (node (ref "U1") (pin "52") (pinfunction "PB13/I2S2_CK/T1CH1N/SPI2_SCK_52") (pintype "passive"))
    )
    (net (code "78") (name "unconnected-(U1-PB14{slash}T1CH2N{slash}SPI2_MISO-Pad53)") (class "Default")
      (node (ref "U1") (pin "53") (pinfunction "PB14/T1CH2N/SPI2_MISO_53") (pintype "passive"))
    )
    (net (code "79") (name "unconnected-(U1-PB15{slash}I2S2_SD{slash}T1CH3N{slash}SPI2_MOSI-Pad54)") (class "Default")
      (node (ref "U1") (pin "54") (pinfunction "PB15/I2S2_SD/T1CH3N/SPI2_MOSI_54") (pintype "passive"))
    )
    (net (code "80") (name "unconnected-(U1-PC4{slash}ADC123_IN14-Pad33)") (class "Default")
      (node (ref "U1") (pin "33") (pinfunction "PC4/ADC123_IN14_33") (pintype "passive"))
    )
    (net (code "81") (name "unconnected-(U1-PC5{slash}ADC123_IN15-Pad34)") (class "Default")
      (node (ref "U1") (pin "34") (pinfunction "PC5/ADC123_IN15_34") (pintype "passive"))
    )
    (net (code "82") (name "unconnected-(U1-PC10{slash}UART4_Tx{slash}SDIO_D2-Pad78)") (class "Default")
      (node (ref "U1") (pin "78") (pinfunction "PC10/UART4_Tx/SDIO_D2_78") (pintype "passive"))
    )
    (net (code "83") (name "unconnected-(U1-PC11{slash}UART4_Rx{slash}SDIO_D3-Pad79)") (class "Default")
      (node (ref "U1") (pin "79") (pinfunction "PC11/UART4_Rx/SDIO_D3_79") (pintype "passive"))
    )
    (net (code "84") (name "unconnected-(U1-PC12{slash}UART5_Tx{slash}SDIO_CK-Pad80)") (class "Default")
      (node (ref "U1") (pin "80") (pinfunction "PC12/UART5_Tx/SDIO_CK_80") (pintype "passive"))
    )
    (net (code "85") (name "unconnected-(U1-PC13-TAMPER-RTC-Pad7)") (class "Default")
      (node (ref "U1") (pin "7") (pinfunction "PC13-TAMPER-RTC_7") (pintype "passive"))
    )
    (net (code "86") (name "unconnected-(U1-PD7{slash}FSMC_NE1{slash}FSMC_NCE2-Pad88)") (class "Default")
      (node (ref "U1") (pin "88") (pinfunction "PD7/FSMC_NE1/FSMC_NCE2_88") (pintype "passive"))
    )
    (net (code "87") (name "unconnected-(U1-PD10{slash}FSMC_D15-Pad57)") (class "Default")
      (node (ref "U1") (pin "57") (pinfunction "PD10/FSMC_D15_57") (pintype "passive"))
    )
    (net (code "88") (name "unconnected-(U1-PD11{slash}FSMC_A16-Pad58)") (class "Default")
      (node (ref "U1") (pin "58") (pinfunction "PD11/FSMC_A16_58") (pintype "passive"))
    )
    (net (code "89") (name "unconnected-(U1-PD12{slash}T4C1{slash}FSMC_A17-Pad59)") (class "Default")
      (node (ref "U1") (pin "59") (pinfunction "PD12/T4C1/FSMC_A17_59") (pintype "passive"))
    )
    (net (code "90") (name "unconnected-(U1-PD13{slash}T4C2{slash}FSMC_A18-Pad60)") (class "Default")
      (node (ref "U1") (pin "60") (pinfunction "PD13/T4C2/FSMC_A18_60") (pintype "passive"))
    )
    (net (code "91") (name "unconnected-(U1-PD15{slash}T4C4{slash}FSMC_D1-Pad62)") (class "Default")
      (node (ref "U1") (pin "62") (pinfunction "PD15/T4C4/FSMC_D1_62") (pintype "passive"))
    )
    (net (code "92") (name "unconnected-(U1-PE0{slash}T4_ETR{slash}FSMC_NBL0-Pad97)") (class "Default")
      (node (ref "U1") (pin "97") (pinfunction "PE0/T4_ETR/FSMC_NBL0_97") (pintype "passive"))
    )
    (net (code "93") (name "unconnected-(U1-PE1{slash}FSMC_NBL1-Pad98)") (class "Default")
      (node (ref "U1") (pin "98") (pinfunction "PE1/FSMC_NBL1_98") (pintype "passive"))
    )
    (net (code "94") (name "unconnected-(U1-PE4{slash}TRACED1{slash}FSMC_A20-Pad3)") (class "Default")
      (node (ref "U1") (pin "3") (pinfunction "PE4/TRACED1/FSMC_A20_3") (pintype "passive"))
    )
    (net (code "95") (name "unconnected-(U1-PE5{slash}TRACED2{slash}FSMC_A21-Pad4)") (class "Default")
      (node (ref "U1") (pin "4") (pinfunction "PE5/TRACED2/FSMC_A21_4") (pintype "passive"))
    )
    (net (code "96") (name "unconnected-(U1-PE6{slash}TRACED3{slash}FSMC_A22-Pad5)") (class "Default")
      (node (ref "U1") (pin "5") (pinfunction "PE6/TRACED3/FSMC_A22_5") (pintype "passive"))
    )
    (net (code "97") (name "unconnected-(U1-PE7{slash}FSMC_D4{slash}T1ETR-Pad38)") (class "Default")
      (node (ref "U1") (pin "38") (pinfunction "PE7/FSMC_D4/T1ETR_38") (pintype "passive"))
    )
    (net (code "98") (name "unconnected-(U1-PE8{slash}FSMC_D5{slash}T1CH1N-Pad39)") (class "Default")
      (node (ref "U1") (pin "39") (pinfunction "PE8/FSMC_D5/T1CH1N_39") (pintype "passive"))
    )
    (net (code "99") (name "unconnected-(U1-PE9{slash}FSMC_D6{slash}T1C1-Pad40)") (class "Default")
      (node (ref "U1") (pin "40") (pinfunction "PE9/FSMC_D6/T1C1_40") (pintype "passive"))
    )
    (net (code "100") (name "unconnected-(U1-PE10{slash}FSMC_D7{slash}T1CH2N-Pad41)") (class "Default")
      (node (ref "U1") (pin "41") (pinfunction "PE10/FSMC_D7/T1CH2N_41") (pintype "passive"))
    )
    (net (code "101") (name "unconnected-(U1-PE11{slash}FSMC_D8{slash}T1C2-Pad42)") (class "Default")
      (node (ref "U1") (pin "42") (pinfunction "PE11/FSMC_D8/T1C2_42") (pintype "passive"))
    )
    (net (code "102") (name "unconnected-(U1-PE12{slash}FSMC_D9{slash}T1CH3N-Pad43)") (class "Default")
      (node (ref "U1") (pin "43") (pinfunction "PE12/FSMC_D9/T1CH3N_43") (pintype "passive"))
    )
    (net (code "103") (name "unconnected-(U1-PE13{slash}FSMC_D10{slash}T1C3-Pad44)") (class "Default")
      (node (ref "U1") (pin "44") (pinfunction "PE13/FSMC_D10/T1C3_44") (pintype "passive"))
    )
    (net (code "104") (name "unconnected-(U1-PE14{slash}FSMC_D11{slash}T1C4-Pad45)") (class "Default")
      (node (ref "U1") (pin "45") (pinfunction "PE14/FSMC_D11/T1C4_45") (pintype "passive"))
    )
    (net (code "105") (name "unconnected-(U1-PE15{slash}FSMC_D12{slash}T1BKIN-Pad46)") (class "Default")
      (node (ref "U1") (pin "46") (pinfunction "PE15/FSMC_D12/T1BKIN_46") (pintype "passive"))
    )
    (net (code "106") (name "unconnected-(U4-Pad5)") (class "Default")
      (node (ref "U4") (pin "5") (pintype "passive"))
    )
    (net (code "107") (name "unconnected-(U4-Pad6)") (class "Default")
      (node (ref "U4") (pin "6") (pintype "passive"))
    )
    (net (code "108") (name "unconnected-(U4-Pad7)") (class "Default")
      (node (ref "U4") (pin "7") (pintype "passive"))
    )
    (net (code "109") (name "unconnected-(USB-NC-Pad4)") (class "Default")
      (node (ref "USB") (pin "4") (pinfunction "NC_4") (pintype "passive"))
    )
  )
)
